# main_board.net
KiCad netlist of a schematic drawn in Altium Designer
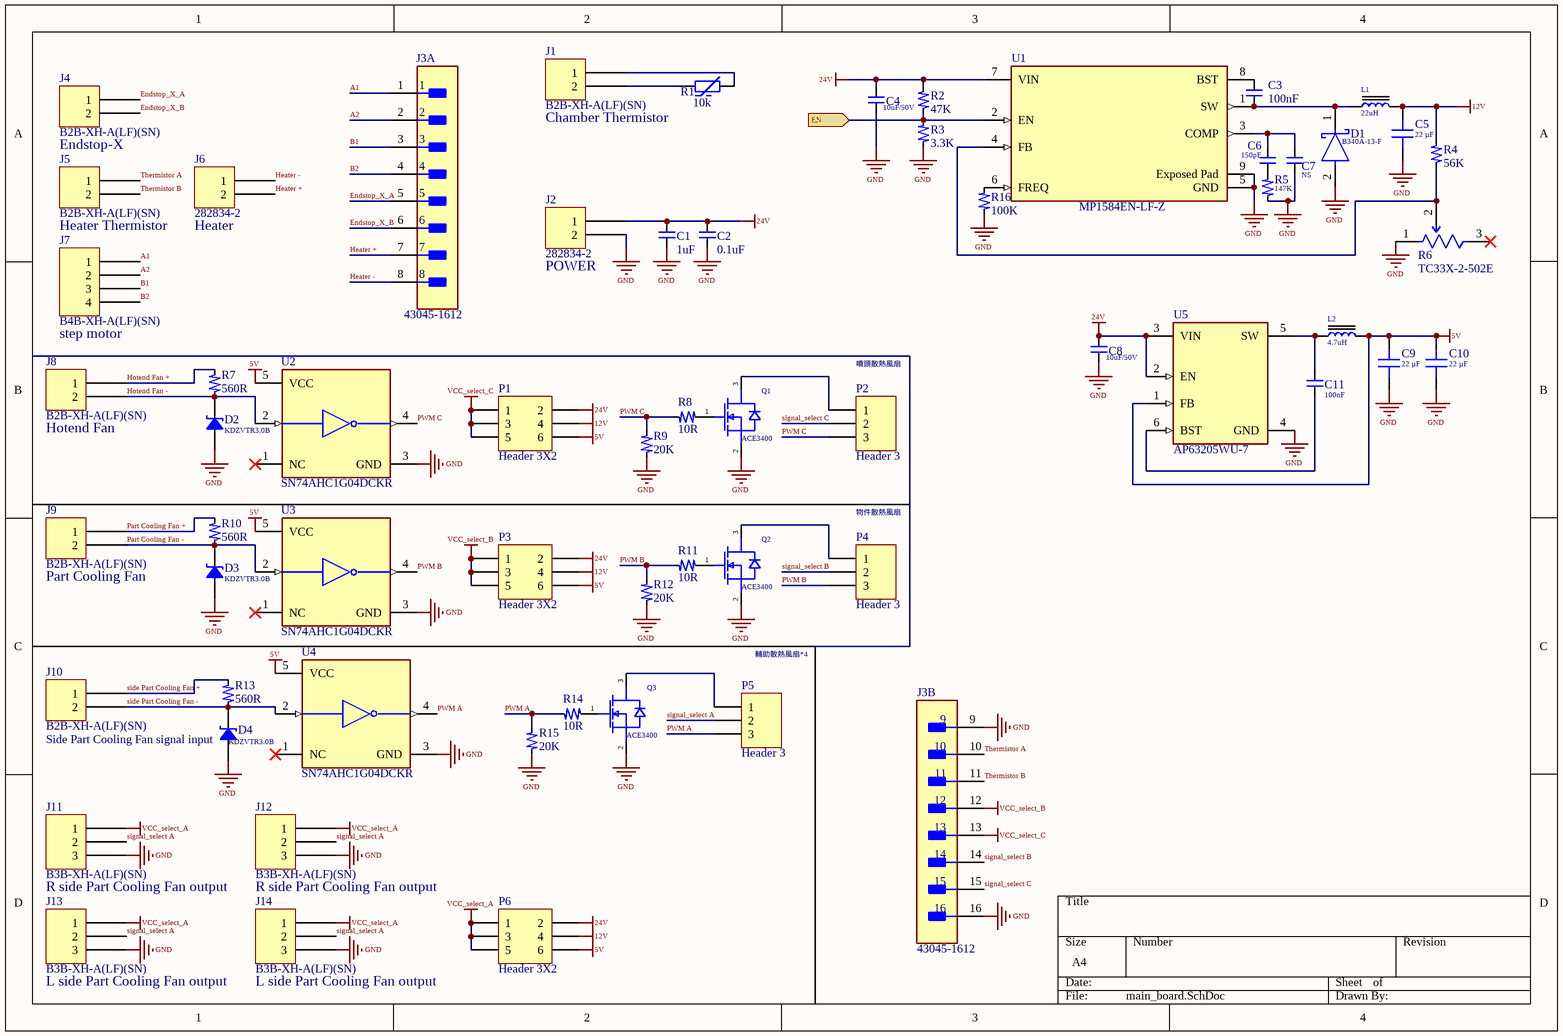
[diagram p0: main_board.SchDoc]

(export (version "E")
  (design (tool "Eeschema 10.0.6"))
  (components
    (comp (ref "C1") (value "1uF") (footprint "0603 R") (libsource (lib "SwitchLIB") (part "Capacitors")))
    (comp (ref "C2") (value "0.1uF") (footprint "0603 R") (libsource (lib "SwitchLIB") (part "Capacitors")))
    (comp (ref "C3") (value "100nF") (footprint "0603 R") (libsource (lib "SwitchLIB") (part "Capacitors")))
    (comp (ref "C4")
      (value "10uF/50V")
      (footprint "0603 R")
      (libsource (lib "SwitchLIB") (part "Capacitors"))
    )
    (comp (ref "C5")
      (value "22 µF")
      (footprint "CAP 1206_3216 - 0.8MM")
      (description "CAP CER 22UF 25V X6S 1206")
      (fields
        (field (name "PART NUMBER") "GRM31CC81E226KE11L")
        (field (name "MANUFACTURER") "Murata Electronics")
        (field (name "LASTUPDATED") "2022/9/19 下午 01:06:42")
      )
      (libsource (lib "Celestial Altium Library - altium_library") (part "Capacitor"))
    )
    (comp (ref "C6") (value "150pF") (footprint "0603 R") (libsource (lib "SwitchLIB") (part "Capacitors")))
    (comp (ref "C7") (value "NS") (footprint "0603 R") (libsource (lib "SwitchLIB") (part "Capacitors")))
    (comp (ref "C8")
      (value "10uF/50V")
      (footprint "0603 R")
      (libsource (lib "SwitchLIB") (part "Capacitors"))
    )
    (comp (ref "C9")
      (value "22 µF")
      (footprint "CAP 1206_3216 - 0.8MM")
      (description "CAP CER 22UF 25V X6S 1206")
      (fields
        (field (name "PART NUMBER") "GRM31CC81E226KE11L")
        (field (name "MANUFACTURER") "Murata Electronics")
        (field (name "LASTUPDATED") "2022/9/19 下午 01:06:42")
      )
      (libsource (lib "Celestial Altium Library - altium_library") (part "Capacitor"))
    )
    (comp (ref "C10")
      (value "22 µF")
      (footprint "CAP 1206_3216 - 0.8MM")
      (description "CAP CER 22UF 25V X6S 1206")
      (fields
        (field (name "PART NUMBER") "GRM31CC81E226KE11L")
        (field (name "MANUFACTURER") "Murata Electronics")
        (field (name "LASTUPDATED") "2022/9/19 下午 01:06:42")
      )
      (libsource (lib "Celestial Altium Library - altium_library") (part "Capacitor"))
    )
    (comp (ref "C11") (value "100nF") (footprint "0603 R") (libsource (lib "SwitchLIB") (part "Capacitors")))
    (comp (ref "D1")
      (value "B340A-13-F")
      (footprint "FP-SMA-MFG")
      (description "DIODE SCHOTTKY 40V 3A SMA")
      (fields (field (name "VOLTAGE") "40V"))
      (libsource (lib "Altium Content Vault") (part "1d6ec82d83fb6aee721767c19dac4b9"))
    )
    (comp (ref "D2")
      (value "KDZVTR3.0B")
      (footprint "SOD123F")
      (description "DIODE ZENER 3V 1W PMDU")
      (fields
        (field (name "MANUFACTURER") "Rohm Semiconductor")
        (field (name "TOLERANCE") "±6.67%")
        (field (name "LASTUPDATED") "2022/9/19 下午 01:47:27")
      )
      (libsource (lib "Celestial Altium Library - altium_library") (part "Diode Zener"))
    )
    (comp (ref "D3")
      (value "KDZVTR3.0B")
      (footprint "SOD123F")
      (description "DIODE ZENER 3V 1W PMDU")
      (fields
        (field (name "MANUFACTURER") "Rohm Semiconductor")
        (field (name "TOLERANCE") "±6.67%")
        (field (name "LASTUPDATED") "2022/9/19 下午 01:47:27")
      )
      (libsource (lib "Celestial Altium Library - altium_library") (part "Diode Zener"))
    )
    (comp (ref "D4")
      (value "KDZVTR3.0B")
      (footprint "SOD123F")
      (description "DIODE ZENER 3V 1W PMDU")
      (fields
        (field (name "MANUFACTURER") "Rohm Semiconductor")
        (field (name "TOLERANCE") "±6.67%")
        (field (name "LASTUPDATED") "2022/9/19 下午 01:47:27")
      )
      (libsource (lib "Celestial Altium Library - altium_library") (part "Diode Zener"))
    )
    (comp (ref "J1")
      (value "B2B-XH-A(LF)(SN)")
      (footprint "JST XH B2B-XH-A")
      (description "CONN HEADER VERT 2POS 2.5MM")
      (fields
        (field (name "MANUFACTURER") "JST Sales America Inc.")
        (field (name "LASTUPDATED") "2020/1/12 下午 11:46:08")
      )
      (libsource (lib "Celestial Altium Library - altium_library") (part "2 Pin"))
    )
    (comp (ref "J2")
      (value "282834-2")
      (footprint "TE 282834-2")
      (description "TERM BLK 2P SIDE ENT 2.54MM PCB")
      (fields
        (field (name "MANUFACTURER") "TE Connectivity AMP Connectors")
        (field (name "VOLTAGE") "150V")
        (field (name "LASTUPDATED") "2020/1/15 上午 04:15:38")
      )
      (libsource (lib "Celestial Altium Library - altium_library") (part "2 Pin"))
    )
    (comp (ref "J3")
      (value "43045-1612")
      (footprint "FP-43045-1612-MFG")
      (description "CONN HEADER VERT 16POS 3MM")
      (libsource (lib "") (part "91eeaff556776ba2144699b5bd25858_1"))
    )
    (comp (ref "J4")
      (value "B2B-XH-A(LF)(SN)")
      (footprint "JST XH B2B-XH-A")
      (description "CONN HEADER VERT 2POS 2.5MM")
      (fields
        (field (name "MANUFACTURER") "JST Sales America Inc.")
        (field (name "LASTUPDATED") "2020/1/12 下午 11:46:08")
      )
      (libsource (lib "Celestial Altium Library - altium_library") (part "2 Pin"))
    )
    (comp (ref "J5")
      (value "B2B-XH-A(LF)(SN)")
      (footprint "JST XH B2B-XH-A")
      (description "CONN HEADER VERT 2POS 2.5MM")
      (fields
        (field (name "MANUFACTURER") "JST Sales America Inc.")
        (field (name "LASTUPDATED") "2020/1/12 下午 11:46:08")
      )
      (libsource (lib "Celestial Altium Library - altium_library") (part "2 Pin"))
    )
    (comp (ref "J6")
      (value "282834-2")
      (footprint "TE 282834-2")
      (description "TERM BLK 2P SIDE ENT 2.54MM PCB")
      (fields
        (field (name "MANUFACTURER") "TE Connectivity AMP Connectors")
        (field (name "VOLTAGE") "150V")
        (field (name "LASTUPDATED") "2020/1/15 上午 04:15:38")
      )
      (libsource (lib "Celestial Altium Library - altium_library") (part "2 Pin"))
    )
    (comp (ref "J7")
      (value "B4B-XH-A(LF)(SN)")
      (footprint "JST XH B4B-XH-A")
      (description "CONN HEADER VERT 4POS 2.5MM")
      (fields
        (field (name "MANUFACTURER") "JST Sales America Inc.")
        (field (name "LASTUPDATED") "2020/1/12 下午 11:46:34")
      )
      (libsource (lib "Celestial Altium Library - altium_library") (part "4 Pin"))
    )
    (comp (ref "J8")
      (value "B2B-XH-A(LF)(SN)")
      (footprint "JST XH B2B-XH-A")
      (description "CONN HEADER VERT 2POS 2.5MM")
      (fields
        (field (name "MANUFACTURER") "JST Sales America Inc.")
        (field (name "LASTUPDATED") "2020/1/12 下午 11:46:08")
      )
      (libsource (lib "Celestial Altium Library - altium_library") (part "2 Pin"))
    )
    (comp (ref "J9")
      (value "B2B-XH-A(LF)(SN)")
      (footprint "JST XH B2B-XH-A")
      (description "CONN HEADER VERT 2POS 2.5MM")
      (fields
        (field (name "MANUFACTURER") "JST Sales America Inc.")
        (field (name "LASTUPDATED") "2020/1/12 下午 11:46:08")
      )
      (libsource (lib "Celestial Altium Library - altium_library") (part "2 Pin"))
    )
    (comp (ref "J10")
      (value "B2B-XH-A(LF)(SN)")
      (footprint "JST XH B2B-XH-A")
      (description "CONN HEADER VERT 2POS 2.5MM")
      (fields
        (field (name "MANUFACTURER") "JST Sales America Inc.")
        (field (name "LASTUPDATED") "2020/1/12 下午 11:46:08")
      )
      (libsource (lib "Celestial Altium Library - altium_library") (part "2 Pin"))
    )
    (comp (ref "J11")
      (value "B3B-XH-A(LF)(SN)")
      (footprint "JST XH B3B-XH-A")
      (description "CONN HEADER VERT 3POS 2.5MM")
      (fields
        (field (name "MANUFACTURER") "JST Sales America Inc.")
        (field (name "LASTUPDATED") "2020/1/12 下午 11:46:22")
      )
      (libsource (lib "Celestial Altium Library - altium_library") (part "3 Pin"))
    )
    (comp (ref "J12")
      (value "B3B-XH-A(LF)(SN)")
      (footprint "JST XH B3B-XH-A")
      (description "CONN HEADER VERT 3POS 2.5MM")
      (fields
        (field (name "MANUFACTURER") "JST Sales America Inc.")
        (field (name "LASTUPDATED") "2020/1/12 下午 11:46:22")
      )
      (libsource (lib "Celestial Altium Library - altium_library") (part "3 Pin"))
    )
    (comp (ref "J13")
      (value "B3B-XH-A(LF)(SN)")
      (footprint "JST XH B3B-XH-A")
      (description "CONN HEADER VERT 3POS 2.5MM")
      (fields
        (field (name "MANUFACTURER") "JST Sales America Inc.")
        (field (name "LASTUPDATED") "2020/1/12 下午 11:46:22")
      )
      (libsource (lib "Celestial Altium Library - altium_library") (part "3 Pin"))
    )
    (comp (ref "J14")
      (value "B3B-XH-A(LF)(SN)")
      (footprint "JST XH B3B-XH-A")
      (description "CONN HEADER VERT 3POS 2.5MM")
      (fields
        (field (name "MANUFACTURER") "JST Sales America Inc.")
        (field (name "LASTUPDATED") "2020/1/12 下午 11:46:22")
      )
      (libsource (lib "Celestial Altium Library - altium_library") (part "3 Pin"))
    )
    (comp (ref "L1") (value "22uH") (footprint "0850 I") (libsource (lib "SwitchLIB") (part "Inductor")))
    (comp (ref "L2") (value "4.7uH") (footprint "0630 I") (libsource (lib "SwitchLIB") (part "Inductor")))
    (comp (ref "P1")
      (value "Header 3X2")
      (footprint "HDR2X3")
      (description "Header, 3-Pin, Dual row")
      (fields (field (name "PUBLISHER") "Altium Limited"))
      (libsource (lib "Miscellaneous Connectors") (part "Header 3X2"))
    )
    (comp (ref "P2")
      (value "Header 3")
      (footprint "HDR1X3")
      (description "Header, 3-Pin")
      (fields (field (name "PUBLISHER") "Altium Limited"))
      (libsource (lib "Miscellaneous Connectors") (part "Header 3"))
    )
    (comp (ref "P3")
      (value "Header 3X2")
      (footprint "HDR2X3")
      (description "Header, 3-Pin, Dual row")
      (fields (field (name "PUBLISHER") "Altium Limited"))
      (libsource (lib "Miscellaneous Connectors") (part "Header 3X2"))
    )
    (comp (ref "P4")
      (value "Header 3")
      (footprint "HDR1X3")
      (description "Header, 3-Pin")
      (fields (field (name "PUBLISHER") "Altium Limited"))
      (libsource (lib "Miscellaneous Connectors") (part "Header 3"))
    )
    (comp (ref "P5")
      (value "Header 3")
      (footprint "HDR1X3")
      (description "Header, 3-Pin")
      (fields (field (name "PUBLISHER") "Altium Limited"))
      (libsource (lib "Miscellaneous Connectors") (part "Header 3"))
    )
    (comp (ref "P6")
      (value "Header 3X2")
      (footprint "HDR2X3")
      (description "Header, 3-Pin, Dual row")
      (fields (field (name "PUBLISHER") "Altium Limited"))
      (libsource (lib "Miscellaneous Connectors") (part "Header 3X2"))
    )
    (comp (ref "Q1") (value "ACE3400") (footprint "SOT23-3") (libsource (lib "SwitchLIB") (part "ACE3400")))
    (comp (ref "Q2") (value "ACE3400") (footprint "SOT23-3") (libsource (lib "SwitchLIB") (part "ACE3400")))
    (comp (ref "Q3") (value "ACE3400") (footprint "SOT23-3") (libsource (lib "SwitchLIB") (part "ACE3400")))
    (comp (ref "R1")
      (value "10k")
      (footprint "NTC 0805_2012")
      (description "CASE EIA 0805 B= 1% ,10K? 5%")
      (fields
        (field (name "PART NUMBER") "NTCG203NF103JTDS")
        (field (name "MANUFACTURER") "TDK Corporation")
        (field (name "LASTUPDATED") "2020/8/30 下午 09:02:56")
      )
      (libsource (lib "Celestial Altium Library - altium_library") (part "Thermistor"))
    )
    (comp (ref "R2") (value "47K") (footprint "0603 R") (libsource (lib "SwitchLIB") (part "Resistors")))
    (comp (ref "R3") (value "3.3K") (footprint "0603 R") (libsource (lib "SwitchLIB") (part "Resistors")))
    (comp (ref "R4") (value "56K") (footprint "0603 R") (libsource (lib "SwitchLIB") (part "Resistors")))
    (comp (ref "R5") (value "147K") (footprint "0603 R") (libsource (lib "SwitchLIB") (part "Resistors")))
    (comp (ref "R6")
      (value "TC33X-2-502E")
      (footprint "FP-TC33X-2-MFG")
      (description "TRIMMER 5K OHM 0.1W J LEAD TOP")
      (fields (field (name "TOLERANCE") "25%"))
      (libsource (lib "Altium Content Vault") (part "13357d81287629c2fd191d242cfa50c"))
    )
    (comp (ref "R7") (value "560R") (footprint "0603 R") (libsource (lib "SwitchLIB") (part "Resistors")))
    (comp (ref "R8") (value "10R") (footprint "0603 R") (libsource (lib "SwitchLIB") (part "Resistors")))
    (comp (ref "R9") (value "20K") (footprint "0603 R") (libsource (lib "SwitchLIB") (part "Resistors")))
    (comp (ref "R10") (value "560R") (footprint "0603 R") (libsource (lib "SwitchLIB") (part "Resistors")))
    (comp (ref "R11") (value "10R") (footprint "0603 R") (libsource (lib "SwitchLIB") (part "Resistors")))
    (comp (ref "R12") (value "20K") (footprint "0603 R") (libsource (lib "SwitchLIB") (part "Resistors")))
    (comp (ref "R13") (value "560R") (footprint "0603 R") (libsource (lib "SwitchLIB") (part "Resistors")))
    (comp (ref "R14") (value "10R") (footprint "0603 R") (libsource (lib "SwitchLIB") (part "Resistors")))
    (comp (ref "R15") (value "20K") (footprint "0603 R") (libsource (lib "SwitchLIB") (part "Resistors")))
    (comp (ref "R16") (value "100K") (footprint "0603 R") (libsource (lib "SwitchLIB") (part "Resistors")))
    (comp (ref "U1")
      (value "MP1584EN-LF-Z")
      (footprint "FP-MP1584EN-LF-Z-MFG")
      (description "IC REG BUCK ADJ 3A")
      (fields
        (field (name "OCTOPART") "https://octopart.com/mp1584en-lf-z-monolithic+power+systems-18629680")
        (field (name "MANUFACTURER") "Monolithic Power Systems")
      )
      (libsource (lib "Altium Content Vault") (part "4a11bbc70e04dd5d8e18f8ee926335f"))
    )
    (comp (ref "U2")
      (value "SN74AHC1G04DCKR")
      (footprint "FP-DCK0005A-MFG")
      (description "IC INVERTER 1CH 1-INP SC70-5")
      (fields
        (field (name "OCTOPART") "https://octopart.com/sn74ahc1g04dckr-texas+instruments-464403")
        (field (name "MANUFACTURER") "Texas Instruments")
      )
      (libsource (lib "Altium Content Vault") (part "8f1f303614983814af90222e701d255"))
    )
    (comp (ref "U3")
      (value "SN74AHC1G04DCKR")
      (footprint "FP-DCK0005A-MFG")
      (description "IC INVERTER 1CH 1-INP SC70-5")
      (fields
        (field (name "OCTOPART") "https://octopart.com/sn74ahc1g04dckr-texas+instruments-464403")
        (field (name "MANUFACTURER") "Texas Instruments")
      )
      (libsource (lib "Altium Content Vault") (part "8f1f303614983814af90222e701d255"))
    )
    (comp (ref "U4")
      (value "SN74AHC1G04DCKR")
      (footprint "FP-DCK0005A-MFG")
      (description "IC INVERTER 1CH 1-INP SC70-5")
      (fields
        (field (name "OCTOPART") "https://octopart.com/sn74ahc1g04dckr-texas+instruments-464403")
        (field (name "MANUFACTURER") "Texas Instruments")
      )
      (libsource (lib "Altium Content Vault") (part "8f1f303614983814af90222e701d255"))
    )
    (comp (ref "U5")
      (value "AP63205WU-7")
      (footprint "FP-TSOT26-MFG")
      (description "IC REG BUCK 5V 2A TSOT26")
      (fields
        (field (name "MANUFACTURER") "Diodes Inc.")
        (field (name "OCTOPART") "https://octopart.com/ap63205wu-7-diodes+inc.-98099551")
      )
      (libsource (lib "Altium Content Vault") (part "029bc9fbfa4a99dbb8b3a24c2adb655"))
    )
  )
  (nets
    (net (code "1") (name "/A1") (class "Default")
      (node (ref "J3") (pin "1") (pinfunction "1_1") (pintype "passive"))
      (node (ref "J7") (pin "1") (pinfunction "1_1") (pintype "passive"))
    )
    (net (code "2") (name "/A2") (class "Default")
      (node (ref "J3") (pin "2") (pinfunction "2_2") (pintype "passive"))
      (node (ref "J7") (pin "2") (pinfunction "2_2") (pintype "passive"))
    )
    (net (code "3") (name "/B1") (class "Default")
      (node (ref "J3") (pin "3") (pinfunction "3_3") (pintype "passive"))
      (node (ref "J7") (pin "3") (pinfunction "3_3") (pintype "passive"))
    )
    (net (code "4") (name "/B2") (class "Default")
      (node (ref "J3") (pin "4") (pinfunction "4_4") (pintype "passive"))
      (node (ref "J7") (pin "4") (pinfunction "4_4") (pintype "passive"))
    )
    (net (code "5") (name "/EN") (class "Default")
      (node (ref "R2") (pin "2") (pinfunction "2_2") (pintype "passive"))
      (node (ref "R3") (pin "1") (pinfunction "1_1") (pintype "passive"))
      (node (ref "U1") (pin "2") (pinfunction "EN_2") (pintype "input"))
    )
    (net (code "6") (name "/Endstop_X_A") (class "Default")
      (node (ref "J3") (pin "5") (pinfunction "5_5") (pintype "passive"))
      (node (ref "J4") (pin "1") (pinfunction "1_1") (pintype "passive"))
    )
    (net (code "7") (name "/Endstop_X_B") (class "Default")
      (node (ref "J3") (pin "6") (pinfunction "6_6") (pintype "passive"))
      (node (ref "J4") (pin "2") (pinfunction "2_2") (pintype "passive"))
    )
    (net (code "8") (name "/Heater +") (class "Default")
      (node (ref "J3") (pin "7") (pinfunction "7_7") (pintype "passive"))
      (node (ref "J6") (pin "2") (pinfunction "2_2") (pintype "passive"))
    )
    (net (code "9") (name "/Heater -") (class "Default")
      (node (ref "J3") (pin "8") (pinfunction "8_8") (pintype "passive"))
      (node (ref "J6") (pin "1") (pinfunction "1_1") (pintype "passive"))
    )
    (net (code "10") (name "/Hotend Fan +") (class "Default")
      (node (ref "J8") (pin "1") (pinfunction "1_1") (pintype "passive"))
      (node (ref "R7") (pin "2") (pinfunction "2_2") (pintype "passive"))
    )
    (net (code "11") (name "/Hotend Fan -") (class "Default")
      (node (ref "D2") (pin "2") (pinfunction "2_2") (pintype "passive"))
      (node (ref "J8") (pin "2") (pinfunction "2_2") (pintype "passive"))
      (node (ref "R7") (pin "1") (pinfunction "1_1") (pintype "passive"))
      (node (ref "U2") (pin "2") (pinfunction "A_2") (pintype "input"))
    )
    (net (code "12") (name "/PWM A") (class "Default")
      (node (ref "P5") (pin "3") (pinfunction "3_3") (pintype "passive"))
      (node (ref "R14") (pin "2") (pinfunction "2_2") (pintype "passive"))
      (node (ref "R15") (pin "2") (pinfunction "2_2") (pintype "passive"))
      (node (ref "U4") (pin "4") (pinfunction "Y_4") (pintype "output"))
    )
    (net (code "13") (name "/PWM B") (class "Default")
      (node (ref "P4") (pin "3") (pinfunction "3_3") (pintype "passive"))
      (node (ref "R11") (pin "2") (pinfunction "2_2") (pintype "passive"))
      (node (ref "R12") (pin "2") (pinfunction "2_2") (pintype "passive"))
      (node (ref "U3") (pin "4") (pinfunction "Y_4") (pintype "output"))
    )
    (net (code "14") (name "/PWM C") (class "Default")
      (node (ref "P2") (pin "3") (pinfunction "3_3") (pintype "passive"))
      (node (ref "R8") (pin "2") (pinfunction "2_2") (pintype "passive"))
      (node (ref "R9") (pin "2") (pinfunction "2_2") (pintype "passive"))
      (node (ref "U2") (pin "4") (pinfunction "Y_4") (pintype "output"))
    )
    (net (code "15") (name "/Part Cooling Fan +") (class "Default")
      (node (ref "J9") (pin "1") (pinfunction "1_1") (pintype "passive"))
      (node (ref "R10") (pin "2") (pinfunction "2_2") (pintype "passive"))
    )
    (net (code "16") (name "/Part Cooling Fan -") (class "Default")
      (node (ref "D3") (pin "2") (pinfunction "2_2") (pintype "passive"))
      (node (ref "J9") (pin "2") (pinfunction "2_2") (pintype "passive"))
      (node (ref "R10") (pin "1") (pinfunction "1_1") (pintype "passive"))
      (node (ref "U3") (pin "2") (pinfunction "A_2") (pintype "input"))
    )
    (net (code "17") (name "/Thermistor A") (class "Default")
      (node (ref "J3") (pin "10") (pinfunction "10_10") (pintype "passive"))
      (node (ref "J5") (pin "1") (pinfunction "1_1") (pintype "passive"))
    )
    (net (code "18") (name "/Thermistor B") (class "Default")
      (node (ref "J3") (pin "11") (pinfunction "11_11") (pintype "passive"))
      (node (ref "J5") (pin "2") (pinfunction "2_2") (pintype "passive"))
    )
    (net (code "19") (name "/side Part Cooling Fan +") (class "Default")
      (node (ref "J10") (pin "1") (pinfunction "1_1") (pintype "passive"))
      (node (ref "R13") (pin "2") (pinfunction "2_2") (pintype "passive"))
    )
    (net (code "20") (name "/side Part Cooling Fan -") (class "Default")
      (node (ref "D4") (pin "2") (pinfunction "2_2") (pintype "passive"))
      (node (ref "J10") (pin "2") (pinfunction "2_2") (pintype "passive"))
      (node (ref "R13") (pin "1") (pinfunction "1_1") (pintype "passive"))
      (node (ref "U4") (pin "2") (pinfunction "A_2") (pintype "input"))
    )
    (net (code "21") (name "/signal_select A") (class "Default")
      (node (ref "J11") (pin "2") (pinfunction "2_2") (pintype "passive"))
      (node (ref "J12") (pin "2") (pinfunction "2_2") (pintype "passive"))
      (node (ref "J13") (pin "2") (pinfunction "2_2") (pintype "passive"))
      (node (ref "J14") (pin "2") (pinfunction "2_2") (pintype "passive"))
      (node (ref "P5") (pin "2") (pinfunction "2_2") (pintype "passive"))
    )
    (net (code "22") (name "/signal_select B") (class "Default")
      (node (ref "J3") (pin "14") (pinfunction "14_14") (pintype "passive"))
      (node (ref "P4") (pin "2") (pinfunction "2_2") (pintype "passive"))
    )
    (net (code "23") (name "/signal_select C") (class "Default")
      (node (ref "J3") (pin "15") (pinfunction "15_15") (pintype "passive"))
      (node (ref "P2") (pin "2") (pinfunction "2_2") (pintype "passive"))
    )
    (net (code "24") (name "5V") (class "Default")
      (node (ref "C10") (pin "2") (pinfunction "2_2") (pintype "passive"))
      (node (ref "C9") (pin "2") (pinfunction "2_2") (pintype "passive"))
      (node (ref "L2") (pin "2") (pinfunction "2_2") (pintype "passive"))
      (node (ref "P1") (pin "6") (pinfunction "6_6") (pintype "passive"))
      (node (ref "P3") (pin "6") (pinfunction "6_6") (pintype "passive"))
      (node (ref "P6") (pin "6") (pinfunction "6_6") (pintype "passive"))
      (node (ref "U2") (pin "5") (pinfunction "VCC_5") (pintype "power_in"))
      (node (ref "U3") (pin "5") (pinfunction "VCC_5") (pintype "power_in"))
      (node (ref "U4") (pin "5") (pinfunction "VCC_5") (pintype "power_in"))
      (node (ref "U5") (pin "1") (pinfunction "FB_1") (pintype "input"))
    )
    (net (code "25") (name "12V") (class "Default")
      (node (ref "C5") (pin "2") (pinfunction "2_2") (pintype "passive"))
      (node (ref "L1") (pin "2") (pinfunction "2_2") (pintype "passive"))
      (node (ref "P1") (pin "4") (pinfunction "4_4") (pintype "passive"))
      (node (ref "P3") (pin "4") (pinfunction "4_4") (pintype "passive"))
      (node (ref "P6") (pin "4") (pinfunction "4_4") (pintype "passive"))
      (node (ref "R4") (pin "2") (pinfunction "2_2") (pintype "passive"))
    )
    (net (code "26") (name "24V") (class "Default")
      (node (ref "C1") (pin "2") (pinfunction "2_2") (pintype "passive"))
      (node (ref "C2") (pin "2") (pinfunction "2_2") (pintype "passive"))
      (node (ref "C4") (pin "2") (pinfunction "2_2") (pintype "passive"))
      (node (ref "C8") (pin "2") (pinfunction "2_2") (pintype "passive"))
      (node (ref "J2") (pin "1") (pinfunction "1_1") (pintype "passive"))
      (node (ref "P1") (pin "2") (pinfunction "2_2") (pintype "passive"))
      (node (ref "P3") (pin "2") (pinfunction "2_2") (pintype "passive"))
      (node (ref "P6") (pin "2") (pinfunction "2_2") (pintype "passive"))
      (node (ref "R2") (pin "1") (pinfunction "1_1") (pintype "passive"))
      (node (ref "U1") (pin "7") (pinfunction "VIN_7") (pintype "power_in"))
      (node (ref "U5") (pin "2") (pinfunction "EN_2") (pintype "input"))
      (node (ref "U5") (pin "3") (pinfunction "VIN_3") (pintype "power_in"))
    )
    (net (code "27") (name "GND") (class "Default")
      (node (ref "C1") (pin "1") (pinfunction "1_1") (pintype "passive"))
      (node (ref "C10") (pin "1") (pinfunction "1_1") (pintype "passive"))
      (node (ref "C2") (pin "1") (pinfunction "1_1") (pintype "passive"))
      (node (ref "C4") (pin "1") (pinfunction "1_1") (pintype "passive"))
      (node (ref "C5") (pin "1") (pinfunction "1_1") (pintype "passive"))
      (node (ref "C7") (pin "1") (pinfunction "1_1") (pintype "passive"))
      (node (ref "C8") (pin "1") (pinfunction "1_1") (pintype "passive"))
      (node (ref "C9") (pin "1") (pinfunction "1_1") (pintype "passive"))
      (node (ref "D1") (pin "2") (pinfunction "A_2") (pintype "passive"))
      (node (ref "D2") (pin "1") (pinfunction "1_1") (pintype "passive"))
      (node (ref "D3") (pin "1") (pinfunction "1_1") (pintype "passive"))
      (node (ref "D4") (pin "1") (pinfunction "1_1") (pintype "passive"))
      (node (ref "J11") (pin "3") (pinfunction "3_3") (pintype "passive"))
      (node (ref "J12") (pin "3") (pinfunction "3_3") (pintype "passive"))
      (node (ref "J13") (pin "3") (pinfunction "3_3") (pintype "passive"))
      (node (ref "J14") (pin "3") (pinfunction "3_3") (pintype "passive"))
      (node (ref "J2") (pin "2") (pinfunction "2_2") (pintype "passive"))
      (node (ref "J3") (pin "16") (pinfunction "16_16") (pintype "passive"))
      (node (ref "J3") (pin "9") (pinfunction "9_9") (pintype "passive"))
      (node (ref "Q1") (pin "2") (pinfunction "S_2") (pintype "passive"))
      (node (ref "Q2") (pin "2") (pinfunction "S_2") (pintype "passive"))
      (node (ref "Q3") (pin "2") (pinfunction "S_2") (pintype "passive"))
      (node (ref "R12") (pin "1") (pinfunction "1_1") (pintype "passive"))
      (node (ref "R15") (pin "1") (pinfunction "1_1") (pintype "passive"))
      (node (ref "R16") (pin "2") (pinfunction "2_2") (pintype "passive"))
      (node (ref "R3") (pin "2") (pinfunction "2_2") (pintype "passive"))
      (node (ref "R5") (pin "2") (pinfunction "2_2") (pintype "passive"))
      (node (ref "R6") (pin "1") (pinfunction "CCW_1") (pintype "passive"))
      (node (ref "R9") (pin "1") (pinfunction "1_1") (pintype "passive"))
      (node (ref "U1") (pin "5") (pinfunction "GND_5") (pintype "power_in"))
      (node (ref "U1") (pin "9") (pinfunction "Exposed_Pad_9") (pintype "power_in"))
      (node (ref "U2") (pin "3") (pinfunction "GND_3") (pintype "power_in"))
      (node (ref "U3") (pin "3") (pinfunction "GND_3") (pintype "power_in"))
      (node (ref "U4") (pin "3") (pinfunction "GND_3") (pintype "power_in"))
      (node (ref "U5") (pin "4") (pinfunction "GND_4") (pintype "power_in"))
    )
    (net (code "28") (name "Net-(C6-Pad1)") (class "Default")
      (node (ref "C6") (pin "1") (pinfunction "1_1") (pintype "passive"))
      (node (ref "R5") (pin "1") (pinfunction "1_1") (pintype "passive"))
    )
    (net (code "29") (name "Net-(D1-C)") (class "Default")
      (node (ref "C3") (pin "1") (pinfunction "1_1") (pintype "passive"))
      (node (ref "D1") (pin "1") (pinfunction "C_1") (pintype "passive"))
      (node (ref "L1") (pin "1") (pinfunction "1_1") (pintype "passive"))
      (node (ref "U1") (pin "1") (pinfunction "SW_1") (pintype "output"))
    )
    (net (code "30") (name "Net-(J1-Pad1)") (class "Default")
      (node (ref "J1") (pin "1") (pinfunction "1_1") (pintype "passive"))
      (node (ref "R1") (pin "2") (pinfunction "2_2") (pintype "passive"))
    )
    (net (code "31") (name "Net-(J1-Pad2)") (class "Default")
      (node (ref "J1") (pin "2") (pinfunction "2_2") (pintype "passive"))
      (node (ref "R1") (pin "1") (pinfunction "1_1") (pintype "passive"))
    )
    (net (code "32") (name "Net-(Q1-D)") (class "Default")
      (node (ref "P2") (pin "1") (pinfunction "1_1") (pintype "passive"))
      (node (ref "Q1") (pin "3") (pinfunction "D_3") (pintype "passive"))
    )
    (net (code "33") (name "Net-(Q1-G)") (class "Default")
      (node (ref "Q1") (pin "1") (pinfunction "G_1") (pintype "passive"))
      (node (ref "R8") (pin "1") (pinfunction "1_1") (pintype "passive"))
    )
    (net (code "34") (name "Net-(Q2-D)") (class "Default")
      (node (ref "P4") (pin "1") (pinfunction "1_1") (pintype "passive"))
      (node (ref "Q2") (pin "3") (pinfunction "D_3") (pintype "passive"))
    )
    (net (code "35") (name "Net-(Q2-G)") (class "Default")
      (node (ref "Q2") (pin "1") (pinfunction "G_1") (pintype "passive"))
      (node (ref "R11") (pin "1") (pinfunction "1_1") (pintype "passive"))
    )
    (net (code "36") (name "Net-(Q3-D)") (class "Default")
      (node (ref "P5") (pin "1") (pinfunction "1_1") (pintype "passive"))
      (node (ref "Q3") (pin "3") (pinfunction "D_3") (pintype "passive"))
    )
    (net (code "37") (name "Net-(Q3-G)") (class "Default")
      (node (ref "Q3") (pin "1") (pinfunction "G_1") (pintype "passive"))
      (node (ref "R14") (pin "1") (pinfunction "1_1") (pintype "passive"))
    )
    (net (code "38") (name "Net-(R6-WIPER)") (class "Default")
      (node (ref "R4") (pin "1") (pinfunction "1_1") (pintype "passive"))
      (node (ref "R6") (pin "2") (pinfunction "WIPER_2") (pintype "passive"))
      (node (ref "U1") (pin "4") (pinfunction "FB_4") (pintype "input"))
    )
    (net (code "39") (name "Net-(U1-BST)") (class "Default")
      (node (ref "C3") (pin "2") (pinfunction "2_2") (pintype "passive"))
      (node (ref "U1") (pin "8") (pinfunction "BST_8") (pintype "power_in"))
    )
    (net (code "40") (name "Net-(U1-COMP)") (class "Default")
      (node (ref "C6") (pin "2") (pinfunction "2_2") (pintype "passive"))
      (node (ref "C7") (pin "2") (pinfunction "2_2") (pintype "passive"))
      (node (ref "U1") (pin "3") (pinfunction "COMP_3") (pintype "output"))
    )
    (net (code "41") (name "Net-(U1-FREQ)") (class "Default")
      (node (ref "R16") (pin "1") (pinfunction "1_1") (pintype "passive"))
      (node (ref "U1") (pin "6") (pinfunction "FREQ_6") (pintype "input"))
    )
    (net (code "42") (name "Net-(U5-BST)") (class "Default")
      (node (ref "C11") (pin "1") (pinfunction "1_1") (pintype "passive"))
      (node (ref "U5") (pin "6") (pinfunction "BST_6") (pintype "input"))
    )
    (net (code "43") (name "Net-(U5-SW)") (class "Default")
      (node (ref "C11") (pin "2") (pinfunction "2_2") (pintype "passive"))
      (node (ref "L2") (pin "1") (pinfunction "1_1") (pintype "passive"))
      (node (ref "U5") (pin "5") (pinfunction "SW_5") (pintype "power_in"))
    )
    (net (code "44") (name "VCC_select_A") (class "Default")
      (node (ref "J11") (pin "1") (pinfunction "1_1") (pintype "passive"))
      (node (ref "J12") (pin "1") (pinfunction "1_1") (pintype "passive"))
      (node (ref "J13") (pin "1") (pinfunction "1_1") (pintype "passive"))
      (node (ref "J14") (pin "1") (pinfunction "1_1") (pintype "passive"))
      (node (ref "P6") (pin "1") (pinfunction "1_1") (pintype "passive"))
      (node (ref "P6") (pin "3") (pinfunction "3_3") (pintype "passive"))
      (node (ref "P6") (pin "5") (pinfunction "5_5") (pintype "passive"))
    )
    (net (code "45") (name "VCC_select_B") (class "Default")
      (node (ref "J3") (pin "12") (pinfunction "12_12") (pintype "passive"))
      (node (ref "P3") (pin "1") (pinfunction "1_1") (pintype "passive"))
      (node (ref "P3") (pin "3") (pinfunction "3_3") (pintype "passive"))
      (node (ref "P3") (pin "5") (pinfunction "5_5") (pintype "passive"))
    )
    (net (code "46") (name "VCC_select_C") (class "Default")
      (node (ref "J3") (pin "13") (pinfunction "13_13") (pintype "passive"))
      (node (ref "P1") (pin "1") (pinfunction "1_1") (pintype "passive"))
      (node (ref "P1") (pin "3") (pinfunction "3_3") (pintype "passive"))
      (node (ref "P1") (pin "5") (pinfunction "5_5") (pintype "passive"))
    )
    (net (code "47") (name "unconnected-(R6-CW-Pad3)") (class "Default")
      (node (ref "R6") (pin "3") (pinfunction "CW_3") (pintype "passive+no_connect"))
    )
    (net (code "48") (name "unconnected-(U2-NC-Pad1)") (class "Default")
      (node (ref "U2") (pin "1") (pinfunction "NC_1") (pintype "passive+no_connect"))
    )
    (net (code "49") (name "unconnected-(U3-NC-Pad1)") (class "Default")
      (node (ref "U3") (pin "1") (pinfunction "NC_1") (pintype "passive+no_connect"))
    )
    (net (code "50") (name "unconnected-(U4-NC-Pad1)") (class "Default")
      (node (ref "U4") (pin "1") (pinfunction "NC_1") (pintype "passive+no_connect"))
    )
  )
)
